# Sensor_Board.net
KiCad netlist of a schematic drawn in Altium Designer
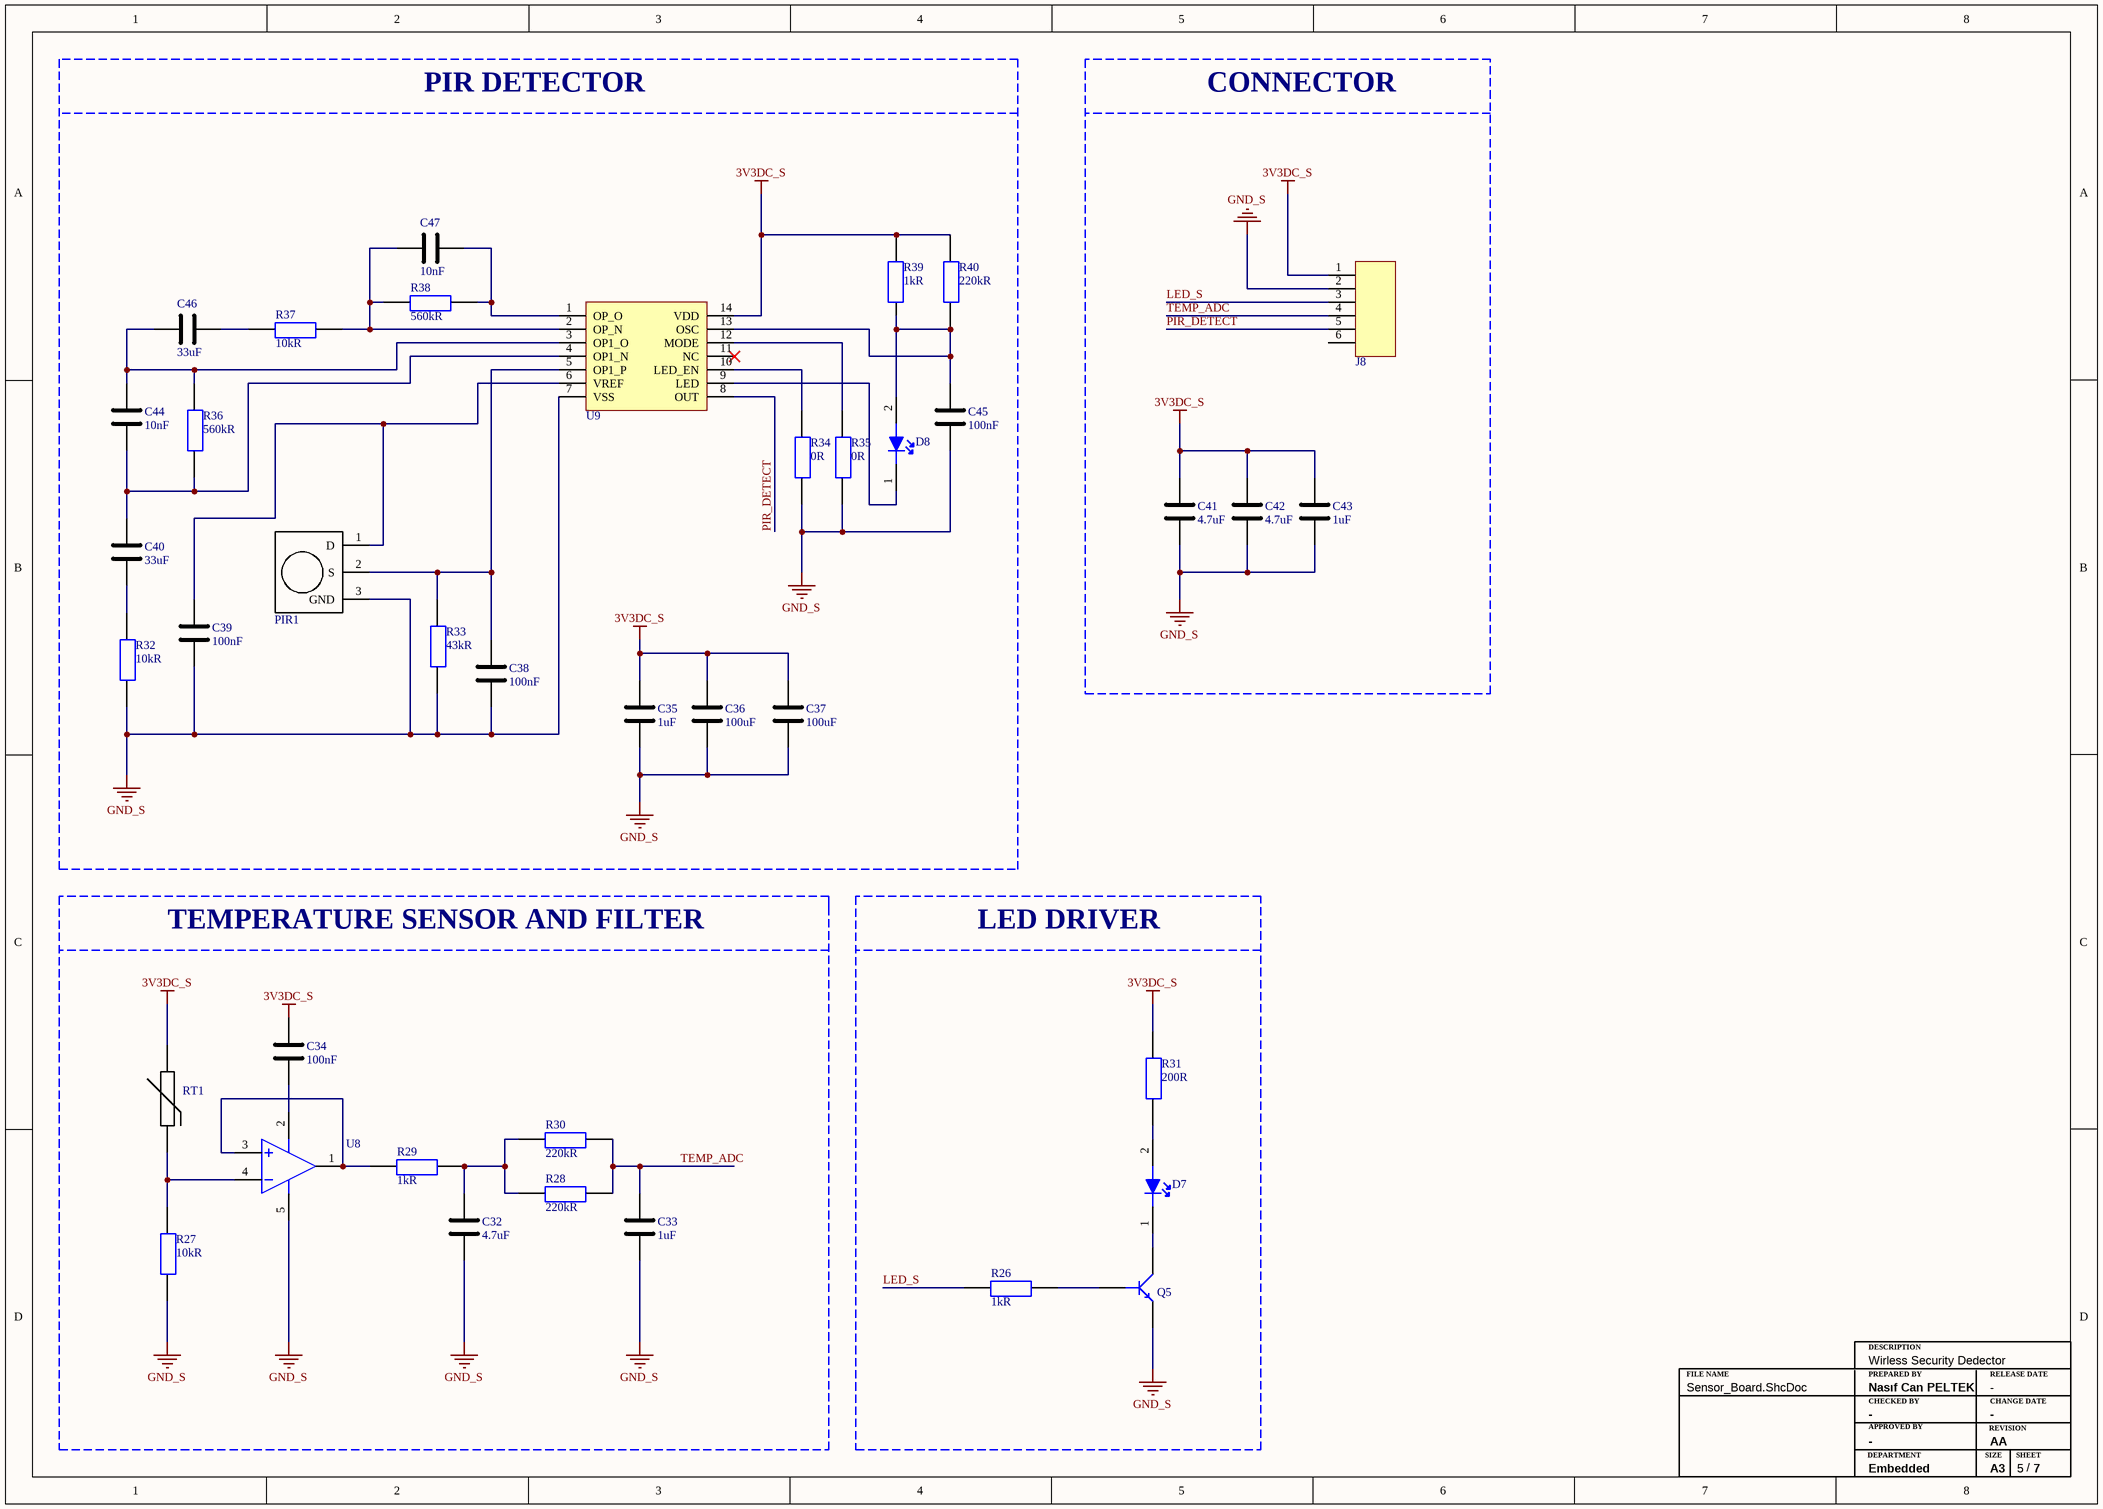
[diagram p0: Sensor_Board.SchDoc]

(export (version "E")
  (design (tool "Eeschema 10.0.6"))
  (components
    (comp (ref "C32")
      (value "CL21A475KAQNNNE")
      (footprint "CAP_805")
      (description "CAP CER 4.7UF 25V 10% 0805")
      (fields
        (field (name "MANUFACTURER") "Samsung")
        (field (name "TOLERANCE") "10%")
        (field (name "CAPACITANCE") "4.7uF")
        (field (name "DESIGNED BY") "Nasıf Can Peltek")
      )
      (libsource (lib "OV_00_Library") (part "CAP CER 4.7uF 0805"))
    )
    (comp (ref "C33")
      (value "CL21B105KBFNNNE")
      (footprint "CAP_805")
      (description "CAP CER 1UF 50V 10% 0805")
      (fields
        (field (name "MANUFACTURER") "Samsung")
        (field (name "TOLERANCE") "10%")
        (field (name "CAPACITANCE") "1uF")
        (field (name "DESIGNED BY") "Nasıf Can Peltek")
      )
      (libsource (lib "OV_00_Library") (part "CAP CER 1uF 0805"))
    )
    (comp (ref "C34")
      (value "C0603C104K5RAC7867")
      (footprint "CAP_603")
      (description "CAP CER 100nF 50V 10% SMD 0603")
      (fields
        (field (name "MANUFACTURER") "KEMET")
        (field (name "MANUFACTURER PART NUMBER") "C0603C104K5RACTU")
        (field (name "CAPACITANCE") "100nF")
        (field (name "DESIGNED BY") "Nasıf Can Peltek")
      )
      (libsource (lib "OV_00_Library") (part "CAP CER 100nF 0603"))
    )
    (comp (ref "C35")
      (value "CL21B105KBFNNNE")
      (footprint "CAP_805")
      (description "CAP CER 1UF 50V 10% 0805")
      (fields
        (field (name "MANUFACTURER") "Samsung")
        (field (name "TOLERANCE") "10%")
        (field (name "CAPACITANCE") "1uF")
        (field (name "DESIGNED BY") "Nasıf Can Peltek")
      )
      (libsource (lib "OV_00_Library") (part "CAP CER 1uF 0805"))
    )
    (comp (ref "C36")
      (value "1210YD107MAT2A")
      (footprint "CAP_1206")
      (description "CAP CER 100UF 16V 10%1206")
      (fields
        (field (name "MANUFACTURER") "KEMET")
        (field (name "MANUFACTURER PART NUMBER") "C0402C223K5RACTU")
        (field (name "CAPACITANCE") "100uF")
        (field (name "DESIGNED BY") "Nasıf Can Peltek")
      )
      (libsource (lib "OV_00_Library") (part "CAP CER 100 uF 1206"))
    )
    (comp (ref "C37")
      (value "1210YD107MAT2A")
      (footprint "CAP_1206")
      (description "CAP CER 100UF 16V 10%1206")
      (fields
        (field (name "MANUFACTURER") "KEMET")
        (field (name "MANUFACTURER PART NUMBER") "C0402C223K5RACTU")
        (field (name "CAPACITANCE") "100uF")
        (field (name "DESIGNED BY") "Nasıf Can Peltek")
      )
      (libsource (lib "OV_00_Library") (part "CAP CER 100 uF 1206"))
    )
    (comp (ref "C38")
      (value "C0603C104K5RAC7867")
      (footprint "CAP_603")
      (description "CAP CER 100nF 50V 10% SMD 0603")
      (fields
        (field (name "MANUFACTURER") "KEMET")
        (field (name "MANUFACTURER PART NUMBER") "C0603C104K5RACTU")
        (field (name "CAPACITANCE") "100nF")
        (field (name "DESIGNED BY") "Nasıf Can Peltek")
      )
      (libsource (lib "OV_00_Library") (part "CAP CER 100nF 0603"))
    )
    (comp (ref "C39")
      (value "C0603C104K5RAC7867")
      (footprint "CAP_603")
      (description "CAP CER 100nF 50V 10% SMD 0603")
      (fields
        (field (name "MANUFACTURER") "KEMET")
        (field (name "MANUFACTURER PART NUMBER") "C0603C104K5RACTU")
        (field (name "CAPACITANCE") "100nF")
        (field (name "DESIGNED BY") "Nasıf Can Peltek")
      )
      (libsource (lib "OV_00_Library") (part "CAP CER 100nF 0603"))
    )
    (comp (ref "C40")
      (value "C3216X5R1C336M160AB")
      (footprint "CAP_1206")
      (description "CAP CER 33uF 16V 20% SMD 1206")
      (fields
        (field (name "MANUFACTURER") "TDK")
        (field (name "TOLERANCE") "20%")
        (field (name "CAPACITANCE") "33uF")
        (field (name "DESIGNED BY") "Nasıf Can Peltek")
      )
      (libsource (lib "OV_00_Library") (part "CAP CER 33uF 1206"))
    )
    (comp (ref "C41")
      (value "CL21A475KAQNNNE")
      (footprint "CAP_805")
      (description "CAP CER 4.7UF 25V 10% 0805")
      (fields
        (field (name "MANUFACTURER") "Samsung")
        (field (name "TOLERANCE") "10%")
        (field (name "CAPACITANCE") "4.7uF")
        (field (name "DESIGNED BY") "Nasıf Can Peltek")
      )
      (libsource (lib "OV_00_Library") (part "CAP CER 4.7uF 0805"))
    )
    (comp (ref "C42")
      (value "CL21A475KAQNNNE")
      (footprint "CAP_805")
      (description "CAP CER 4.7UF 25V 10% 0805")
      (fields
        (field (name "MANUFACTURER") "Samsung")
        (field (name "TOLERANCE") "10%")
        (field (name "CAPACITANCE") "4.7uF")
        (field (name "DESIGNED BY") "Nasıf Can Peltek")
      )
      (libsource (lib "OV_00_Library") (part "CAP CER 4.7uF 0805"))
    )
    (comp (ref "C43")
      (value "CL21B105KBFNNNE")
      (footprint "CAP_805")
      (description "CAP CER 1UF 50V 10% 0805")
      (fields
        (field (name "MANUFACTURER") "Samsung")
        (field (name "TOLERANCE") "10%")
        (field (name "CAPACITANCE") "1uF")
        (field (name "DESIGNED BY") "Nasıf Can Peltek")
      )
      (libsource (lib "OV_00_Library") (part "CAP CER 1uF 0805"))
    )
    (comp (ref "C44")
      (value "0603B103K160CT")
      (footprint "CAP_603")
      (description "CAP CER 10nF 16V 10% SMD 0603")
      (fields
        (field (name "MANUFACTURER") "Walsin Technologies")
        (field (name "TOLERANCE") "10%")
        (field (name "CAPACITANCE") "10nF")
        (field (name "DESIGNED BY") "Nasıf Can Peltek")
      )
      (libsource (lib "OV_00_Library") (part "CAP CER 10nF 0603"))
    )
    (comp (ref "C45")
      (value "C0603C104K5RAC7867")
      (footprint "CAP_603")
      (description "CAP CER 100nF 50V 10% SMD 0603")
      (fields
        (field (name "MANUFACTURER") "KEMET")
        (field (name "MANUFACTURER PART NUMBER") "C0603C104K5RACTU")
        (field (name "CAPACITANCE") "100nF")
        (field (name "DESIGNED BY") "Nasıf Can Peltek")
      )
      (libsource (lib "OV_00_Library") (part "CAP CER 100nF 0603"))
    )
    (comp (ref "C46")
      (value "C3216X5R1C336M160AB")
      (footprint "CAP_1206")
      (description "CAP CER 33uF 16V 20% SMD 1206")
      (fields
        (field (name "MANUFACTURER") "TDK")
        (field (name "TOLERANCE") "20%")
        (field (name "CAPACITANCE") "33uF")
        (field (name "DESIGNED BY") "Nasıf Can Peltek")
      )
      (libsource (lib "OV_00_Library") (part "CAP CER 33uF 1206"))
    )
    (comp (ref "C47")
      (value "0603B103K160CT")
      (footprint "CAP_603")
      (description "CAP CER 10nF 16V 10% SMD 0603")
      (fields
        (field (name "MANUFACTURER") "Walsin Technologies")
        (field (name "TOLERANCE") "10%")
        (field (name "CAPACITANCE") "10nF")
        (field (name "DESIGNED BY") "Nasıf Can Peltek")
      )
      (libsource (lib "OV_00_Library") (part "CAP CER 10nF 0603"))
    )
    (comp (ref "D7")
      (value "LTST-C171KRKT")
      (footprint "LED_RED_0805 (2012 Metric)")
      (description "LED RED CLEAR 0805 SMD")
      (fields (field (name "MANUFACTURER") "Vishay Lite-On") (field (name "DESIGNED BY") "Nasıf Can Peltek"))
      (libsource (lib "OV_00_Library") (part "LED RED 0805"))
    )
    (comp (ref "D8")
      (value "LTST-C171GKT")
      (footprint "LED_GREEN_0805 (2012 Metric) - duplicate")
      (description "LED GREEN CLEAR 0805 SMD")
      (fields (field (name "MANUFACTURER") "Vishay Lite-On") (field (name "DESIGNED BY") "Nasıf Can Peltek"))
      (libsource (lib "OV_00_Library") (part "LED GREEN 0805"))
    )
    (comp (ref "J8")
      (value "64800611622")
      (footprint "MALE_VERTICAL_6_PIN_CONNECTOR")
      (description "Conn, Header, 6POS, 1ROW, 1.5MM;")
      (fields
        (field (name "MANUFACTURER") "Wurth Electronics")
        (field (name "DESIGNED BY") "Nasıf Can Peltek")
      )
      (libsource (lib "OV_00_Library") (part "64800611622_6PIN_CONN"))
    )
    (comp (ref "PIR1")
      (value "LHI 878/3902")
      (footprint "LHI 878/3902")
      (description "Sensor Pyro Detector Dual Motion")
      (fields
        (field (name "MANUFACTURER") "Excelitas Technology")
        (field (name "DESIGNED BY") "Nasıf Can Peltek")
        (field (name "COMPONENTLINK1URL") "file:///C:/Users/OMEN/Downloads/PYD_1388___7083_Dual_Element_Pyrodetector_Datasheet.pdf")
      )
      (libsource (lib "OV_00_Library") (part "LHI 878/3902"))
    )
    (comp (ref "Q5")
      (value "MMBT3904-7-F")
      (footprint "SOT_23_3")
      (description "NPN Ic=200mA Vceo=40V hfe=100~300 fT=310MHz P=300mW SOT-23")
      (fields (field (name "MANUFACTURER") "Diodes Zetex") (field (name "DESIGNED BY") "Nasıf Can Peltek"))
      (libsource (lib "OV_00_Library") (part "MMBT3904-7-F"))
    )
    (comp (ref "R26")
      (value "RC0603FR-071KL")
      (footprint "RES_603")
      (description "RES SMD 1K OHM 1%  0603 SMD")
      (fields
        (field (name "MANUFACTURER") "Yageo")
        (field (name "TOLERANCE") "1%")
        (field (name "RESISTANCE") "1kR")
        (field (name "DESIGNED BY") "Nasıf Can Peltek")
      )
      (libsource (lib "OV_00_Library") (part "RES 1K 0603"))
    )
    (comp (ref "R27")
      (value "RES 10K 0603")
      (footprint "RES_603")
      (description "RES SMD 10K OHM 1% 1/10W 0603 SMD")
      (fields
        (field (name "MANUFACTURER") "Yageo")
        (field (name "MANUFACTURER PART NUMBER") "RC0603FR-0710KL")
        (field (name "RESISTANCE") "10kR")
        (field (name "DESIGNED BY") "Nasıf Can Peltek")
      )
      (libsource (lib "OV_00_Library") (part "RES 10K 0603"))
    )
    (comp (ref "R28")
      (value "RC0603JR-07220KL")
      (footprint "RES_603")
      (description "RES SMD 220K OHM 5% 0603 SMD")
      (fields
        (field (name "MANUFACTURER") "Yageo")
        (field (name "TOLERANCE") "5%")
        (field (name "RESISTANCE") "220kR")
        (field (name "DESIGNED BY") "Nasıf Can Peltek")
      )
      (libsource (lib "") (part "RES 220K 0603_1"))
    )
    (comp (ref "R29")
      (value "RC0603FR-071KL")
      (footprint "RES_603")
      (description "RES SMD 1K OHM 1%  0603 SMD")
      (fields
        (field (name "MANUFACTURER") "Yageo")
        (field (name "TOLERANCE") "1%")
        (field (name "RESISTANCE") "1kR")
        (field (name "DESIGNED BY") "Nasıf Can Peltek")
      )
      (libsource (lib "OV_00_Library") (part "RES 1K 0603"))
    )
    (comp (ref "R30")
      (value "RC0603JR-07220KL")
      (footprint "RES_603")
      (description "RES SMD 220K OHM 5% 0603 SMD")
      (fields
        (field (name "MANUFACTURER") "Yageo")
        (field (name "TOLERANCE") "5%")
        (field (name "RESISTANCE") "220kR")
        (field (name "DESIGNED BY") "Nasıf Can Peltek")
      )
      (libsource (lib "") (part "RES 220K 0603_1"))
    )
    (comp (ref "R31")
      (value "RC0603JR-07200RL")
      (footprint "RES_603")
      (description "RES SMD 220Ohm OHM 5% 0603 SMD")
      (fields
        (field (name "MANUFACTURER") "Yageo")
        (field (name "TOLERANCE") "5%")
        (field (name "RESISTANCE") "200R")
        (field (name "DESIGNED BY") "Nasıf Can Peltek")
      )
      (libsource (lib "OV_00_Library") (part "RES 200 Ohm 0603"))
    )
    (comp (ref "R32")
      (value "RES 10K 0603")
      (footprint "RES_603")
      (description "RES SMD 10K OHM 1% 1/10W 0603 SMD")
      (fields
        (field (name "MANUFACTURER") "Yageo")
        (field (name "MANUFACTURER PART NUMBER") "RC0603FR-0710KL")
        (field (name "RESISTANCE") "10kR")
        (field (name "DESIGNED BY") "Nasıf Can Peltek")
      )
      (libsource (lib "OV_00_Library") (part "RES 10K 0603"))
    )
    (comp (ref "R33")
      (value "RC0603JR-0743KL")
      (footprint "RES_603")
      (description "RES SMD 43K OHM 5% 0603 SMD")
      (fields
        (field (name "MANUFACTURER") "Yageo")
        (field (name "TOLERANCE") "5%")
        (field (name "RESISTANCE") "43kR")
        (field (name "DESIGNED BY") "Nasıf Can Peltek")
      )
      (libsource (lib "OV_00_Library") (part "RES 43K 0603"))
    )
    (comp (ref "R34")
      (value "RC0603JR-070RL")
      (footprint "RES_603")
      (description "RES SMD 0 OHM JUMPER 1/10W 0603")
      (fields
        (field (name "MANUFACTURER") "Yageo")
        (field (name "TOLERANCE") "1%")
        (field (name "RESISTANCE") "0R")
        (field (name "DESIGNED BY") "Nasıf Can Peltek")
      )
      (libsource (lib "OV_00_Library") (part "RES 0R 0603"))
    )
    (comp (ref "R35")
      (value "RC0603JR-070RL")
      (footprint "RES_603")
      (description "RES SMD 0 OHM JUMPER 1/10W 0603")
      (fields
        (field (name "MANUFACTURER") "Yageo")
        (field (name "TOLERANCE") "1%")
        (field (name "RESISTANCE") "0R")
        (field (name "DESIGNED BY") "Nasıf Can Peltek")
      )
      (libsource (lib "OV_00_Library") (part "RES 0R 0603"))
    )
    (comp (ref "R36")
      (value "RC0603JR-07560KL")
      (footprint "RES_603")
      (description "RES 156K OHM 5% 0603 SMD")
      (fields
        (field (name "MANUFACTURER") "Yageo")
        (field (name "TOLERANCE") "5%")
        (field (name "RESISTANCE") "560kR")
        (field (name "DESIGNED BY") "Nasıf Can Peltek")
      )
      (libsource (lib "OV_00_Library") (part "RES 560K 0603"))
    )
    (comp (ref "R37")
      (value "RES 10K 0603")
      (footprint "RES_603")
      (description "RES SMD 10K OHM 1% 1/10W 0603 SMD")
      (fields
        (field (name "MANUFACTURER") "Yageo")
        (field (name "MANUFACTURER PART NUMBER") "RC0603FR-0710KL")
        (field (name "RESISTANCE") "10kR")
        (field (name "DESIGNED BY") "Nasıf Can Peltek")
      )
      (libsource (lib "") (part "RES 10K 0603_1"))
    )
    (comp (ref "R38")
      (value "RC0603JR-07560KL")
      (footprint "RES_603")
      (description "RES 156K OHM 5% 0603 SMD")
      (fields
        (field (name "MANUFACTURER") "Yageo")
        (field (name "TOLERANCE") "5%")
        (field (name "RESISTANCE") "560kR")
        (field (name "DESIGNED BY") "Nasıf Can Peltek")
      )
      (libsource (lib "") (part "RES 560K 0603_1"))
    )
    (comp (ref "R39")
      (value "RC0603FR-071KL")
      (footprint "RES_603")
      (description "RES SMD 1K OHM 1%  0603 SMD")
      (fields
        (field (name "MANUFACTURER") "Yageo")
        (field (name "TOLERANCE") "1%")
        (field (name "RESISTANCE") "1kR")
        (field (name "DESIGNED BY") "Nasıf Can Peltek")
      )
      (libsource (lib "") (part "RES 1K 0603_1"))
    )
    (comp (ref "R40")
      (value "RC0603JR-07220KL")
      (footprint "RES_603")
      (description "RES SMD 220K OHM 5% 0603 SMD")
      (fields
        (field (name "MANUFACTURER") "Yageo")
        (field (name "TOLERANCE") "5%")
        (field (name "RESISTANCE") "220kR")
        (field (name "DESIGNED BY") "Nasıf Can Peltek")
      )
      (libsource (lib "OV_00_Library") (part "RES 220K 0603"))
    )
    (comp (ref "RT1")
      (value "TFPT1206L1002FM")
      (footprint "RES_1206")
      (description "Thermistor PTC 10K Ohm 1% 2-Pin 1206 Surface Mount Solder Pad T/R Automotive")
      (fields
        (field (name "MANUFACTURER") "Vishay Dale")
        (field (name "TOLERANCE") "1%")
        (field (name "DESIGNED BY") "Nasıf Can Peltek")
      )
      (libsource (lib "OV_00_Library") (part "TFPT1206L1002FM"))
    )
    (comp (ref "U8")
      (value "OPA314AIDBVR")
      (footprint "SOT_23_5")
      (description "IC OPAMP GP 3MHZ RRO SOT23-5")
      (fields
        (field (name "MANUFACTURER") "Texas Instruments")
        (field (name "DESIGNED BY") "Nasıf Can Peltek")
      )
      (libsource (lib "OV_00_Library") (part "OPA314AIDBVR"))
    )
    (comp (ref "U9")
      (value "NCS36000DRG")
      (footprint "SOIC-14")
      (description "(PIR) Infrared Detector Controller NCS36000 Series Single 5.5V Passive - SOIC-14")
      (fields
        (field (name "MANUFACTURER") "ON Semiconductor")
        (field (name "MANUFACTURER PART NUMBER") "NCS36000DG")
        (field (name "DESIGNED BY") "Nasıf Can Peltek")
      )
      (libsource (lib "OV_00_Library") (part "NCS36000"))
    )
  )
  (nets
    (net (code "1") (name "/LED_S") (class "Default")
      (node (ref "J8") (pin "3") (pintype "passive"))
      (node (ref "R26") (pin "1") (pinfunction "1_1") (pintype "passive"))
    )
    (net (code "2") (name "/PIR_DETECT") (class "Default")
      (node (ref "J8") (pin "5") (pintype "passive"))
      (node (ref "U9") (pin "8") (pinfunction "OUT_8") (pintype "passive"))
    )
    (net (code "3") (name "/TEMP_ADC") (class "Default")
      (node (ref "C33") (pin "2") (pinfunction "2_2") (pintype "passive"))
      (node (ref "J8") (pin "4") (pintype "passive"))
      (node (ref "R28") (pin "2") (pinfunction "2_2") (pintype "passive"))
      (node (ref "R30") (pin "2") (pinfunction "2_2") (pintype "passive"))
    )
    (net (code "4") (name "3V3DC_S") (class "Default")
      (node (ref "C34") (pin "2") (pinfunction "2_2") (pintype "passive"))
      (node (ref "C35") (pin "2") (pinfunction "2_2") (pintype "passive"))
      (node (ref "C36") (pin "2") (pinfunction "2_2") (pintype "passive"))
      (node (ref "C37") (pin "2") (pinfunction "2_2") (pintype "passive"))
      (node (ref "C41") (pin "2") (pinfunction "2_2") (pintype "passive"))
      (node (ref "C42") (pin "2") (pinfunction "2_2") (pintype "passive"))
      (node (ref "C43") (pin "2") (pinfunction "2_2") (pintype "passive"))
      (node (ref "J8") (pin "1") (pintype "passive"))
      (node (ref "R31") (pin "2") (pinfunction "2_2") (pintype "passive"))
      (node (ref "R39") (pin "1") (pinfunction "1_1") (pintype "passive"))
      (node (ref "R40") (pin "2") (pinfunction "2_2") (pintype "passive"))
      (node (ref "RT1") (pin "2") (pinfunction "2_2") (pintype "passive"))
      (node (ref "U9") (pin "14") (pinfunction "VDD_14") (pintype "passive"))
    )
    (net (code "5") (name "GND_S") (class "Default")
      (node (ref "C32") (pin "1") (pinfunction "1_1") (pintype "passive"))
      (node (ref "C33") (pin "1") (pinfunction "1_1") (pintype "passive"))
      (node (ref "C35") (pin "1") (pinfunction "1_1") (pintype "passive"))
      (node (ref "C36") (pin "1") (pinfunction "1_1") (pintype "passive"))
      (node (ref "C37") (pin "1") (pinfunction "1_1") (pintype "passive"))
      (node (ref "C38") (pin "1") (pinfunction "1_1") (pintype "passive"))
      (node (ref "C39") (pin "1") (pinfunction "1_1") (pintype "passive"))
      (node (ref "C41") (pin "1") (pinfunction "1_1") (pintype "passive"))
      (node (ref "C42") (pin "1") (pinfunction "1_1") (pintype "passive"))
      (node (ref "C43") (pin "1") (pinfunction "1_1") (pintype "passive"))
      (node (ref "C45") (pin "1") (pinfunction "1_1") (pintype "passive"))
      (node (ref "J8") (pin "2") (pintype "passive"))
      (node (ref "PIR1") (pin "3") (pinfunction "GND_3") (pintype "passive"))
      (node (ref "Q5") (pin "2") (pinfunction "E_2") (pintype "passive"))
      (node (ref "R27") (pin "1") (pinfunction "1_1") (pintype "passive"))
      (node (ref "R32") (pin "1") (pinfunction "1_1") (pintype "passive"))
      (node (ref "R33") (pin "1") (pinfunction "1_1") (pintype "passive"))
      (node (ref "R34") (pin "1") (pinfunction "1_1") (pintype "passive"))
      (node (ref "R35") (pin "1") (pinfunction "1_1") (pintype "passive"))
      (node (ref "U8") (pin "5") (pinfunction "V+_5") (pintype "passive"))
      (node (ref "U9") (pin "7") (pinfunction "VSS_7") (pintype "passive"))
    )
    (net (code "6") (name "Net-(C32-Pad2)") (class "Default")
      (node (ref "C32") (pin "2") (pinfunction "2_2") (pintype "passive"))
      (node (ref "R28") (pin "1") (pinfunction "1_1") (pintype "passive"))
      (node (ref "R29") (pin "2") (pinfunction "2_2") (pintype "passive"))
      (node (ref "R30") (pin "1") (pinfunction "1_1") (pintype "passive"))
    )
    (net (code "7") (name "Net-(C40-Pad1)") (class "Default")
      (node (ref "C40") (pin "1") (pinfunction "1_1") (pintype "passive"))
      (node (ref "R32") (pin "2") (pinfunction "2_2") (pintype "passive"))
    )
    (net (code "8") (name "Net-(C46-Pad2)") (class "Default")
      (node (ref "C46") (pin "2") (pinfunction "2_2") (pintype "passive"))
      (node (ref "R37") (pin "1") (pinfunction "1_1") (pintype "passive"))
    )
    (net (code "9") (name "Net-(D7-ANODE(+))") (class "Default")
      (node (ref "D7") (pin "2") (pinfunction "ANODE(+)_2") (pintype "passive"))
      (node (ref "R31") (pin "1") (pinfunction "1_1") (pintype "passive"))
    )
    (net (code "10") (name "Net-(D7-CATHODE(-))") (class "Default")
      (node (ref "D7") (pin "1") (pinfunction "CATHODE(-)_1") (pintype "passive"))
      (node (ref "Q5") (pin "3") (pinfunction "C_3") (pintype "passive"))
    )
    (net (code "11") (name "Net-(D8-ANODE(+))") (class "Default")
      (node (ref "C45") (pin "2") (pinfunction "2_2") (pintype "passive"))
      (node (ref "D8") (pin "2") (pinfunction "ANODE(+)_2") (pintype "passive"))
      (node (ref "R39") (pin "2") (pinfunction "2_2") (pintype "passive"))
      (node (ref "R40") (pin "1") (pinfunction "1_1") (pintype "passive"))
      (node (ref "U9") (pin "13") (pinfunction "OSC_13") (pintype "passive"))
    )
    (net (code "12") (name "Net-(D8-CATHODE(-))") (class "Default")
      (node (ref "D8") (pin "1") (pinfunction "CATHODE(-)_1") (pintype "passive"))
      (node (ref "U9") (pin "9") (pinfunction "LED_9") (pintype "passive"))
    )
    (net (code "13") (name "Net-(PIR1-D)") (class "Default")
      (node (ref "C39") (pin "2") (pinfunction "2_2") (pintype "passive"))
      (node (ref "PIR1") (pin "1") (pinfunction "D_1") (pintype "passive"))
      (node (ref "U9") (pin "6") (pinfunction "VREF_6") (pintype "passive"))
    )
    (net (code "14") (name "Net-(PIR1-S)") (class "Default")
      (node (ref "C38") (pin "2") (pinfunction "2_2") (pintype "passive"))
      (node (ref "PIR1") (pin "2") (pinfunction "S_2") (pintype "passive"))
      (node (ref "R33") (pin "2") (pinfunction "2_2") (pintype "passive"))
      (node (ref "U9") (pin "5") (pinfunction "OP1_P_5") (pintype "passive"))
    )
    (net (code "15") (name "Net-(Q5-B)") (class "Default")
      (node (ref "Q5") (pin "1") (pinfunction "B_1") (pintype "passive"))
      (node (ref "R26") (pin "2") (pinfunction "2_2") (pintype "passive"))
    )
    (net (code "16") (name "Net-(U8-IN+)") (class "Default")
      (node (ref "R29") (pin "1") (pinfunction "1_1") (pintype "passive"))
      (node (ref "U8") (pin "1") (pinfunction "OUT_1") (pintype "passive"))
      (node (ref "U8") (pin "3") (pinfunction "IN+_3") (pintype "passive"))
    )
    (net (code "17") (name "Net-(U8-IN-)") (class "Default")
      (node (ref "R27") (pin "2") (pinfunction "2_2") (pintype "passive"))
      (node (ref "RT1") (pin "1") (pinfunction "1_1") (pintype "passive"))
      (node (ref "U8") (pin "4") (pinfunction "IN-_4") (pintype "passive"))
    )
    (net (code "18") (name "Net-(U8-V-)") (class "Default")
      (node (ref "C34") (pin "1") (pinfunction "1_1") (pintype "passive"))
      (node (ref "U8") (pin "2") (pinfunction "V-_2") (pintype "passive"))
    )
    (net (code "19") (name "Net-(U9-LED_EN)") (class "Default")
      (node (ref "R34") (pin "2") (pinfunction "2_2") (pintype "passive"))
      (node (ref "U9") (pin "10") (pinfunction "LED_EN_10") (pintype "passive"))
    )
    (net (code "20") (name "Net-(U9-MODE)") (class "Default")
      (node (ref "R35") (pin "2") (pinfunction "2_2") (pintype "passive"))
      (node (ref "U9") (pin "12") (pinfunction "MODE_12") (pintype "passive"))
    )
    (net (code "21") (name "Net-(U9-OP1_N)") (class "Default")
      (node (ref "C40") (pin "2") (pinfunction "2_2") (pintype "passive"))
      (node (ref "C44") (pin "1") (pinfunction "1_1") (pintype "passive"))
      (node (ref "R36") (pin "1") (pinfunction "1_1") (pintype "passive"))
      (node (ref "U9") (pin "4") (pinfunction "OP1_N_4") (pintype "passive"))
    )
    (net (code "22") (name "Net-(U9-OP1_O)") (class "Default")
      (node (ref "C44") (pin "2") (pinfunction "2_2") (pintype "passive"))
      (node (ref "C46") (pin "1") (pinfunction "1_1") (pintype "passive"))
      (node (ref "R36") (pin "2") (pinfunction "2_2") (pintype "passive"))
      (node (ref "U9") (pin "3") (pinfunction "OP1_O_3") (pintype "passive"))
    )
    (net (code "23") (name "Net-(U9-OP_N)") (class "Default")
      (node (ref "C47") (pin "1") (pinfunction "1_1") (pintype "passive"))
      (node (ref "R37") (pin "2") (pinfunction "2_2") (pintype "passive"))
      (node (ref "R38") (pin "1") (pinfunction "1_1") (pintype "passive"))
      (node (ref "U9") (pin "2") (pinfunction "OP_N_2") (pintype "passive"))
    )
    (net (code "24") (name "Net-(U9-OP_O)") (class "Default")
      (node (ref "C47") (pin "2") (pinfunction "2_2") (pintype "passive"))
      (node (ref "R38") (pin "2") (pinfunction "2_2") (pintype "passive"))
      (node (ref "U9") (pin "1") (pinfunction "OP_O_1") (pintype "passive"))
    )
    (net (code "25") (name "unconnected-(J8-Pad6)") (class "Default")
      (node (ref "J8") (pin "6") (pintype "passive"))
    )
    (net (code "26") (name "unconnected-(U9-NC-Pad11)") (class "Default")
      (node (ref "U9") (pin "11") (pinfunction "NC_11") (pintype "passive+no_connect"))
    )
  )
)
